# ProDoc__V2_0_2025-09-29.net
KiCad netlist of a schematic drawn in EasyEDA Pro
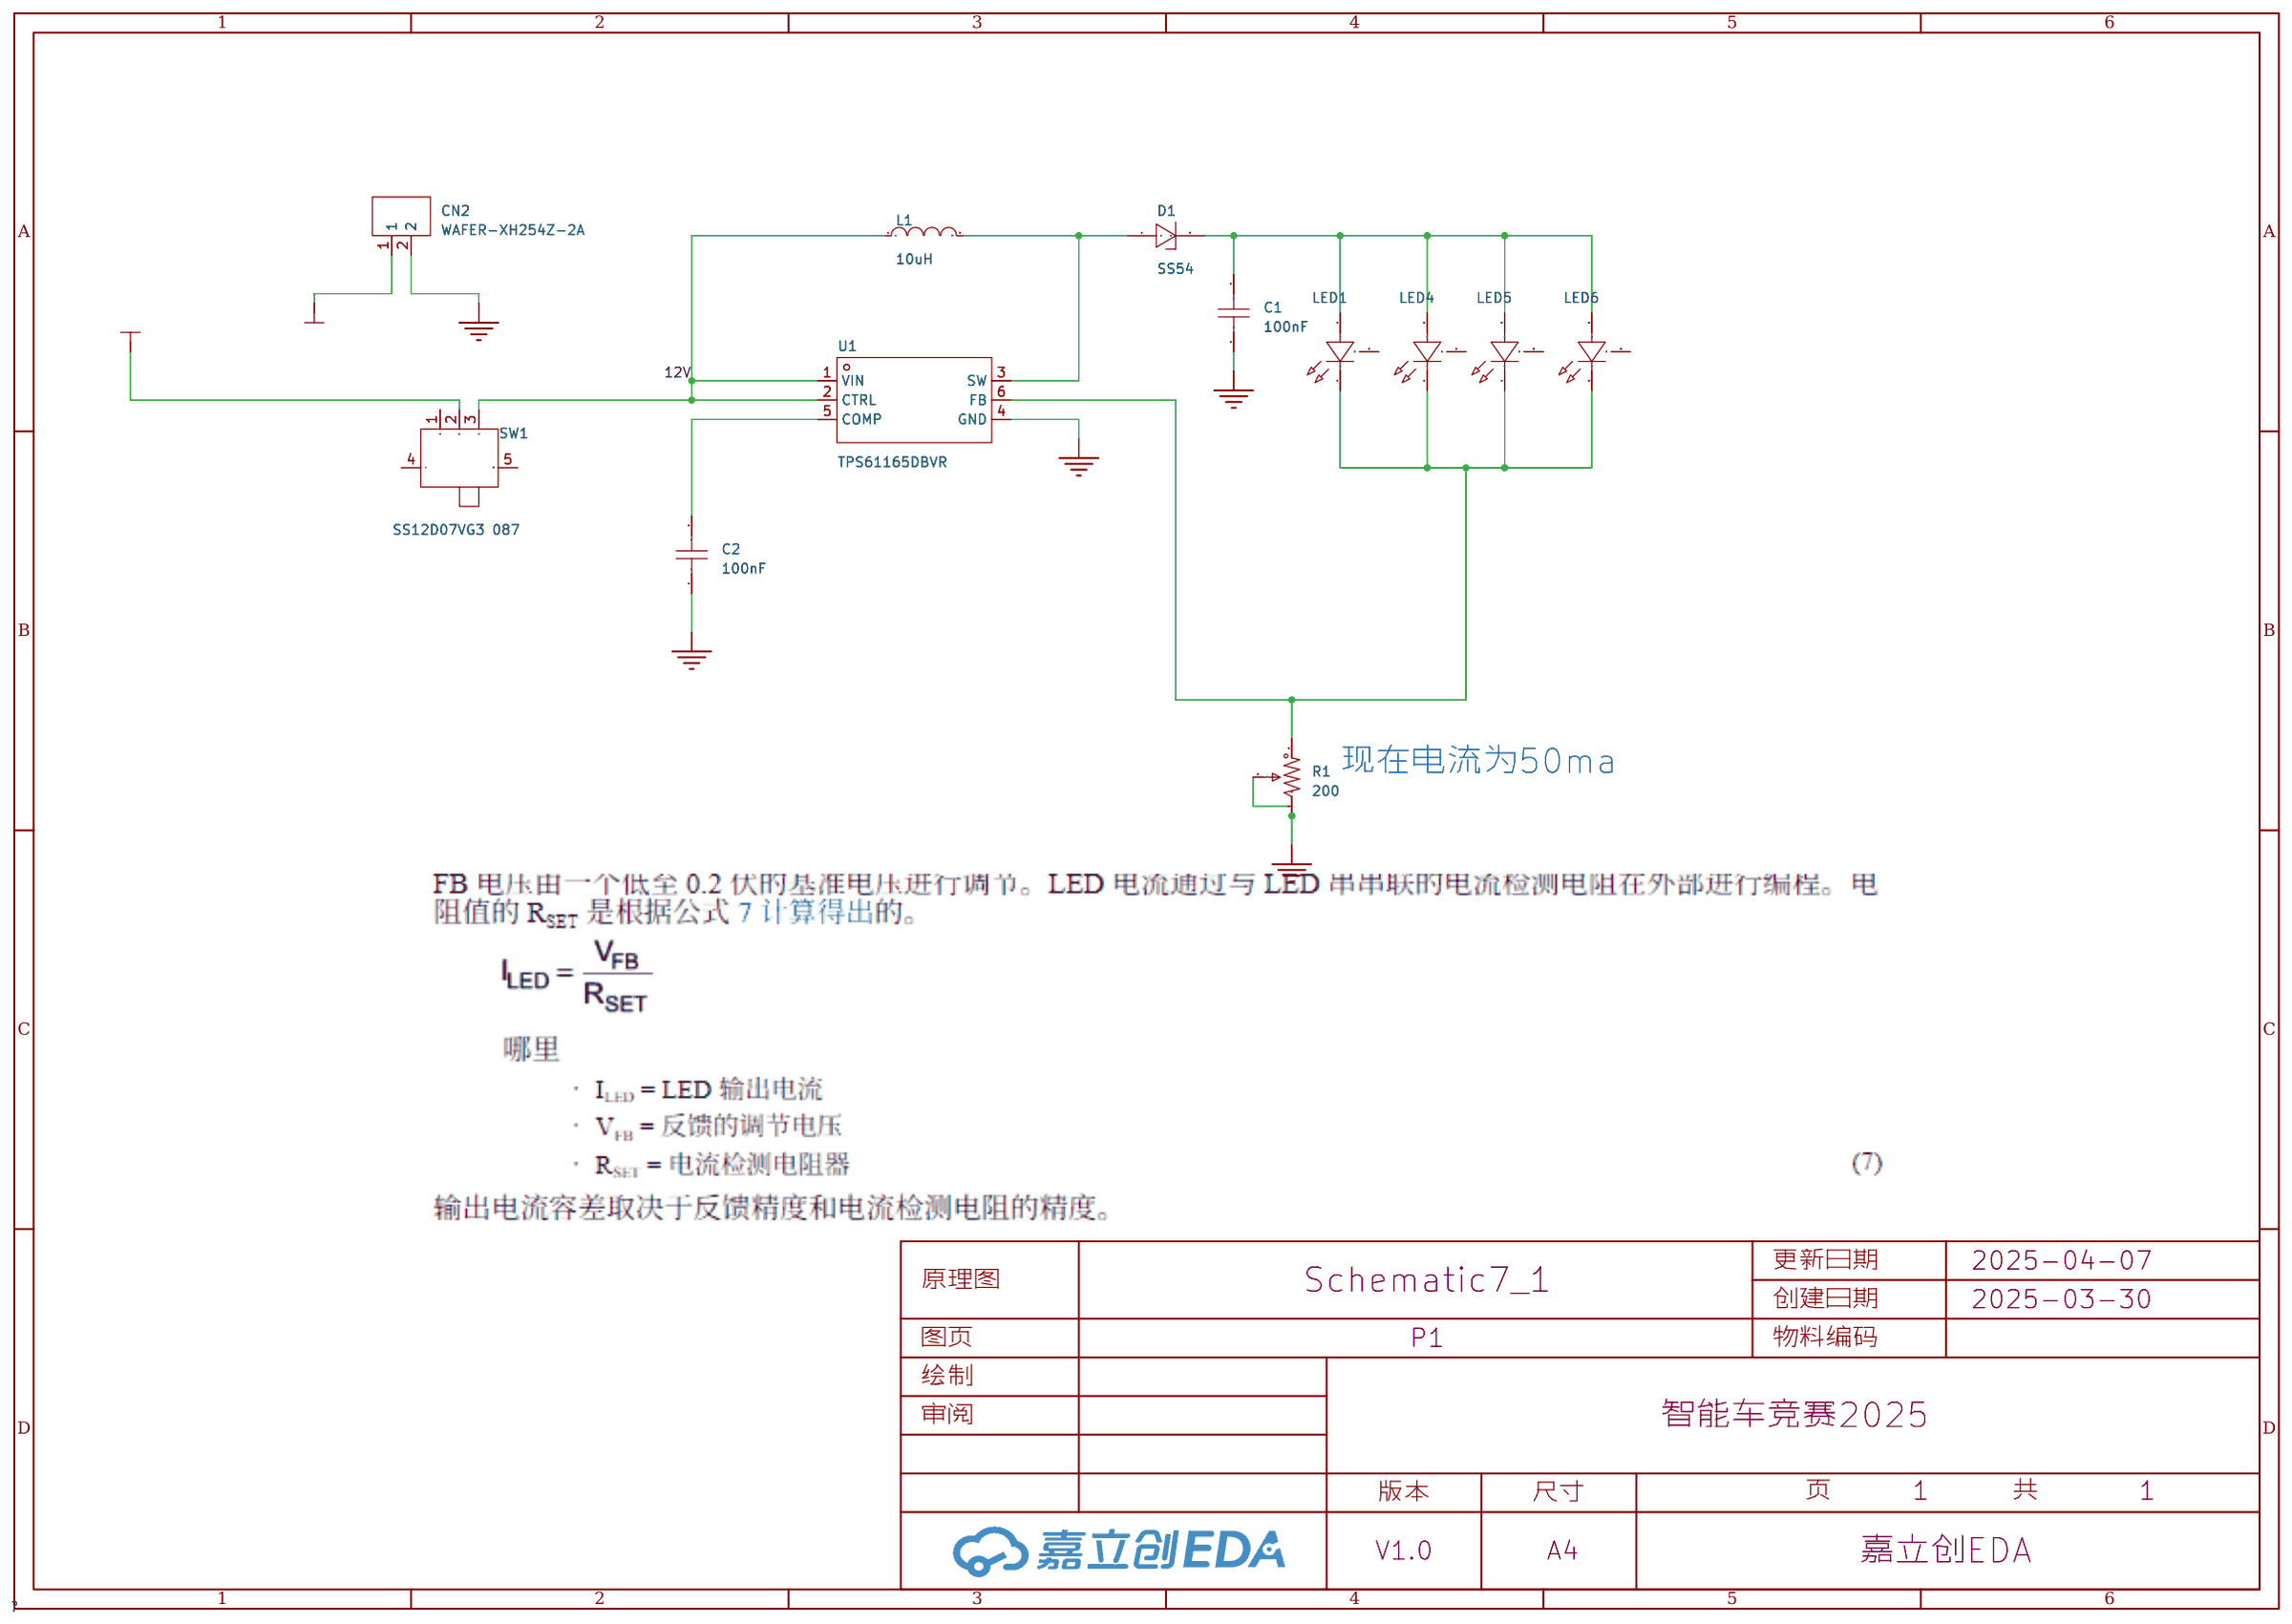
[diagram p0: schematic sheet]

(export (version "E")
  (design (tool "Eeschema 10.0.6"))
  (components
    (comp (ref "C1")
      (value "100nF")
      (footprint "easyedapro:C0805")
      (libsource (lib "easyedapro") (part "CapAcitance"))
    )
    (comp (ref "C2")
      (value "100nF")
      (footprint "easyedapro:C0805")
      (libsource (lib "easyedapro") (part "CapAcitance"))
    )
    (comp (ref "CN2")
      (value "WAFER-XH254Z-2A")
      (footprint "easyedapro:CONN-TH_2P-P2.50_XH-2A_3045048")
      (description "插针结构:1x2P;间距:2.54mm;安装方式:直插;参考系列:XH;总PIN数:2P;排数:1;每排PIN数:2;额定电流:3A;工作温度范围:-25°C~+85°C;")
      (fields (field (name "Manufacturer") "HANBO(汉博)"))
      (libsource (lib "easyedapro") (part "WAFER-XH254Z-2A"))
    )
    (comp (ref "D1")
      (value "SS54")
      (footprint "easyedapro:SMA_L4.3-W2.6-LS5.0-FD")
      (description "二极管配置:独立式;正向压降(Vf):550mV@5.0A;直流反向耐压(Vr):40V;整流电流:5A;")
      (fields (field (name "Manufacturer") "宏迦橙"))
      (libsource (lib "easyedapro") (part "SS54_C7420369"))
    )
    (comp (ref "L1")
      (value "10uH")
      (footprint "easyedapro:IND-SMD_L5.4-W5.2_FXL0530")
      (description "电感值:10uH;精度:±20%;额定电流:3.2A;饱和电流(Isat):3.5A;类型:一体成型电感;")
      (fields (field (name "Manufacturer Part") "FXL0530-100-M") (field (name "Manufacturer") "cjiang(长江微电)"))
      (libsource (lib "easyedapro") (part "FXL0530-100-M"))
    )
    (comp (ref "LED1")
      (value "XL-5730UWC-05")
      (footprint "easyedapro:LED-SMD_3P-L5.7-W3.0-RD")
      (description "发光颜色:白色;功率:500mW;正向电流:150mA;透镜颜色:黄色透镜;色温:6000K~6500K;发光角度:120°;载带方式:正贴;工作温度:-30°C~+85°C;")
      (fields (field (name "Manufacturer") "XINGLIGHT(成兴光)"))
      (libsource (lib "easyedapro") (part "XL-5730UWC-05"))
    )
    (comp (ref "LED4")
      (value "XL-5730UWC-05")
      (footprint "easyedapro:LED-SMD_3P-L5.7-W3.0-RD")
      (description "发光颜色:白色;功率:500mW;正向电流:150mA;透镜颜色:黄色透镜;色温:6000K~6500K;发光角度:120°;载带方式:正贴;工作温度:-30°C~+85°C;")
      (fields (field (name "Manufacturer") "XINGLIGHT(成兴光)"))
      (libsource (lib "easyedapro") (part "XL-5730UWC-05"))
    )
    (comp (ref "LED5")
      (value "XL-5730UWC-05")
      (footprint "easyedapro:LED-SMD_3P-L5.7-W3.0-RD")
      (description "发光颜色:白色;功率:500mW;正向电流:150mA;透镜颜色:黄色透镜;色温:6000K~6500K;发光角度:120°;载带方式:正贴;工作温度:-30°C~+85°C;")
      (fields (field (name "Manufacturer") "XINGLIGHT(成兴光)"))
      (libsource (lib "easyedapro") (part "XL-5730UWC-05"))
    )
    (comp (ref "LED6")
      (value "XL-5730UWC-05")
      (footprint "easyedapro:LED-SMD_3P-L5.7-W3.0-RD")
      (description "发光颜色:白色;功率:500mW;正向电流:150mA;透镜颜色:黄色透镜;色温:6000K~6500K;发光角度:120°;载带方式:正贴;工作温度:-30°C~+85°C;")
      (fields (field (name "Manufacturer") "XINGLIGHT(成兴光)"))
      (libsource (lib "easyedapro") (part "XL-5730UWC-05"))
    )
    (comp (ref "R1")
      (value "200")
      (footprint "easyedapro:RES-ADJ-TH_3296X")
      (description "阻值:5kΩ;精度:±10%;")
      (fields (field (name "Manufacturer Part") "3296X-1-502") (field (name "Manufacturer") "BOCHEN(博晨)"))
      (libsource (lib "easyedapro") (part "3296X-1-502"))
    )
    (comp (ref "SW1")
      (value "SS12D07VG3 087")
      (footprint "easyedapro:SW-TH_SS12D07VG4")
      (description "电路结构:单刀双掷;安装方式:直插;开关颜色:-;额定电流(DC):500mA;额定电压(DC):50V;额定电流(AC):-;额定电压(AC):-;机械寿命:5千次;")
      (fields (field (name "Manufacturer") "SHOU HAN(首韩)"))
      (libsource (lib "easyedapro") (part "SS12D07VG3 087"))
    )
    (comp (ref "U1")
      (value "TPS61165DBVR")
      (footprint "easyedapro:SOT-23-6_L2.9-W1.6-P0.95-LS2.8-BR")
      (description "类型:DC-DC稳压器;输入电压:3V~18V;开关频率:1.2MHz;通道数:1;输出电压:3V~38V;输出电流:1.2A;调光:PWM;拓扑结构:升压;")
      (fields (field (name "Manufacturer") "TI(德州仪器)"))
      (libsource (lib "easyedapro") (part "TPS61165DBVR"))
    )
  )
  (nets
    (net (code "1") (name "/12V") (class "Default")
      (node (ref "L1") (pin "1") (pinfunction "1_1") (pintype "unspecified"))
      (node (ref "SW1") (pin "3") (pinfunction "3_3") (pintype "unspecified"))
      (node (ref "U1") (pin "1") (pinfunction "VIN_1") (pintype "unspecified"))
      (node (ref "U1") (pin "2") (pinfunction "CTRL_2") (pintype "unspecified"))
    )
    (net (code "2") (name "GND") (class "Default")
      (node (ref "C1") (pin "1") (pinfunction "1_1") (pintype "input"))
      (node (ref "C2") (pin "1") (pinfunction "1_1") (pintype "input"))
      (node (ref "CN2") (pin "2") (pinfunction "2_2") (pintype "unspecified"))
      (node (ref "R1") (pin "2") (pinfunction "2_2") (pintype "unspecified"))
      (node (ref "R1") (pin "3") (pinfunction "3_3") (pintype "unspecified"))
      (node (ref "U1") (pin "4") (pinfunction "GND_4") (pintype "unspecified"))
    )
    (net (code "3") (name "Net-(D1-A)") (class "Default")
      (node (ref "D1") (pin "1") (pinfunction "A_1") (pintype "unspecified"))
      (node (ref "L1") (pin "2") (pinfunction "2_2") (pintype "unspecified"))
      (node (ref "U1") (pin "3") (pinfunction "SW_3") (pintype "unspecified"))
    )
    (net (code "4") (name "Net-(D1-K)") (class "Default")
      (node (ref "C1") (pin "2") (pinfunction "2_2") (pintype "input"))
      (node (ref "D1") (pin "2") (pinfunction "K_2") (pintype "unspecified"))
      (node (ref "LED1") (pin "2") (pinfunction "A_2") (pintype "unspecified"))
      (node (ref "LED4") (pin "2") (pinfunction "A_2") (pintype "unspecified"))
      (node (ref "LED5") (pin "2") (pinfunction "A_2") (pintype "unspecified"))
      (node (ref "LED6") (pin "2") (pinfunction "A_2") (pintype "unspecified"))
    )
    (net (code "5") (name "Net-(LED1-K)") (class "Default")
      (node (ref "LED1") (pin "1") (pinfunction "K_1") (pintype "unspecified"))
      (node (ref "LED4") (pin "1") (pinfunction "K_1") (pintype "unspecified"))
      (node (ref "LED5") (pin "1") (pinfunction "K_1") (pintype "unspecified"))
      (node (ref "LED6") (pin "1") (pinfunction "K_1") (pintype "unspecified"))
      (node (ref "R1") (pin "1") (pinfunction "1_1") (pintype "unspecified"))
      (node (ref "U1") (pin "6") (pinfunction "FB_6") (pintype "unspecified"))
    )
    (net (code "6") (name "Net-(U1-COMP)") (class "Default")
      (node (ref "C2") (pin "2") (pinfunction "2_2") (pintype "input"))
      (node (ref "U1") (pin "5") (pinfunction "COMP_5") (pintype "unspecified"))
    )
    (net (code "7") (name "VIN") (class "Default")
      (node (ref "CN2") (pin "1") (pinfunction "1_1") (pintype "unspecified"))
      (node (ref "SW1") (pin "2") (pinfunction "2_2") (pintype "unspecified"))
    )
    (net (code "8") (name "unconnected-(LED1-Pad3)") (class "Default")
      (node (ref "LED1") (pin "3") (pinfunction "3_3") (pintype "unspecified"))
    )
    (net (code "9") (name "unconnected-(LED4-Pad3)") (class "Default")
      (node (ref "LED4") (pin "3") (pinfunction "3_3") (pintype "unspecified"))
    )
    (net (code "10") (name "unconnected-(LED5-Pad3)") (class "Default")
      (node (ref "LED5") (pin "3") (pinfunction "3_3") (pintype "unspecified"))
    )
    (net (code "11") (name "unconnected-(LED6-Pad3)") (class "Default")
      (node (ref "LED6") (pin "3") (pinfunction "3_3") (pintype "unspecified"))
    )
    (net (code "12") (name "unconnected-(SW1-Pad1)") (class "Default")
      (node (ref "SW1") (pin "1") (pinfunction "1_1") (pintype "unspecified"))
    )
    (net (code "13") (name "unconnected-(SW1-Pad4)") (class "Default")
      (node (ref "SW1") (pin "4") (pinfunction "4_4") (pintype "unspecified"))
    )
    (net (code "14") (name "unconnected-(SW1-Pad5)") (class "Default")
      (node (ref "SW1") (pin "5") (pinfunction "5_5") (pintype "unspecified"))
    )
  )
)
